# Motordriver.net
KiCad netlist of a schematic drawn in Altium Designer
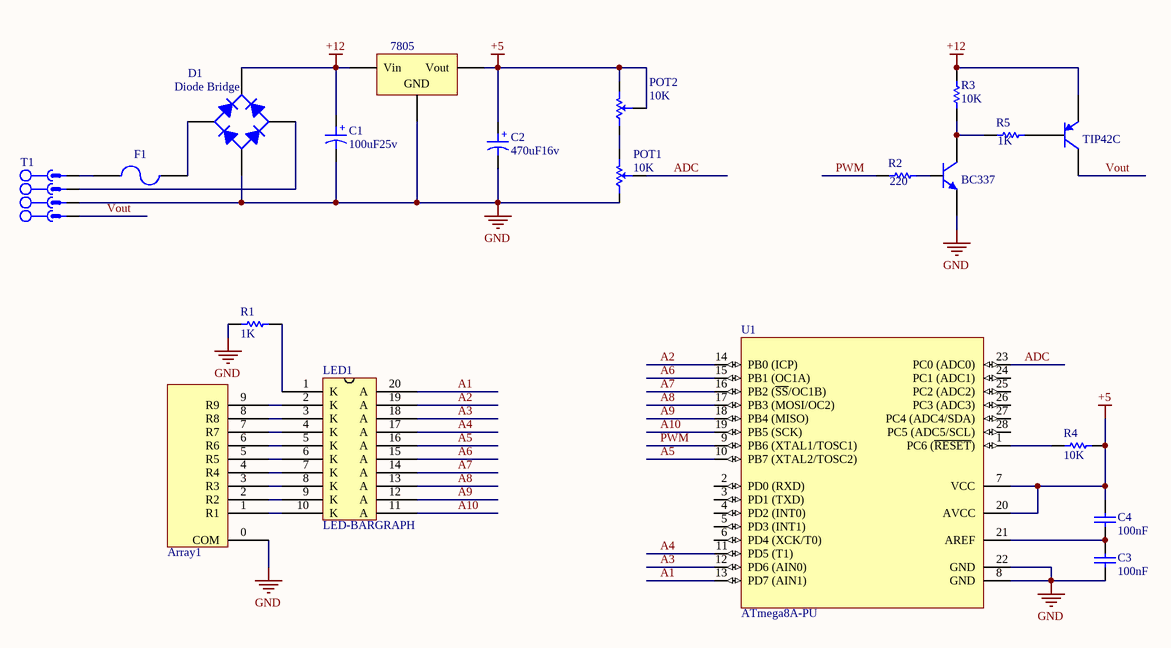
[diagram p0: Motordriver.SchDoc]

(export (version "E")
  (design (tool "Eeschema 10.0.6"))
  (components
    (comp (ref "7805")
      (value "L7805CV")
      (footprint "TO-220 AB WITH HEAT SINK")
      (description "Linear Voltage Regulator IC Positive FIXED Output 5V 1.5A TO-220AB")
      (fields (field (name "MANUFACTURER") "STMicroelectronics") (field (name "DESIGNER") "Abbas Basereh"))
      (libsource (lib "Altium") (part "L7805CV-Linear Voltage Regulator"))
    )
    (comp (ref "Array1")
      (value "Array10pin")
      (footprint "Array")
      (libsource (lib "emadars_Library") (part "Array10pin"))
    )
    (comp (ref "BC337")
      (value "TIP41C")
      (footprint "TO-220 AB WITH HEAT SINK")
      (description "NPN  power transistor")
      (fields (field (name "MANUFACTURER") "STMicroelectronics") (field (name "DESIGNER") "Abbas Basereh"))
      (libsource (lib "Altium") (part "TIP41C"))
    )
    (comp (ref "C1")
      (value "100uF25v")
      (footprint "Cap electrolitic radial 6x7-2.5")
      (description "Cap electrolitic radial")
      (fields (field (name "DESIGNER") "Abbas Basereh"))
      (libsource (lib "Altium") (part "Cap ELECTROLITIC TOTAL SIZE"))
    )
    (comp (ref "C2")
      (value "470uF16v")
      (footprint "Cap electrolitic radial 6x7-2.5")
      (description "Cap electrolitic radial")
      (fields (field (name "DESIGNER") "Abbas Basereh"))
      (libsource (lib "Altium") (part "Cap ELECTROLITIC TOTAL SIZE"))
    )
    (comp (ref "C3")
      (value "100nF")
      (footprint "CAP Ceramic 2.5MM")
      (description "CAP Ceramic Total")
      (fields (field (name "DESIGNER") "Ali Hafizi"))
      (libsource (lib "Altium") (part "CAP CERAMIC TOTAL SIZE"))
    )
    (comp (ref "C4")
      (value "100nF")
      (footprint "CAP Ceramic 2.5MM")
      (description "CAP Ceramic Total")
      (fields (field (name "DESIGNER") "Ali Hafizi"))
      (libsource (lib "Altium") (part "CAP CERAMIC TOTAL SIZE"))
    )
    (comp (ref "D1")
      (value "Diode Bridge")
      (footprint "Bridge Circle Package")
      (description "Full Wave Diode Bridge")
      (fields (field (name "DESIGNER") "Abbas Basereh"))
      (libsource (lib "Altium") (part "Diode Bridge TOTAL SIZE"))
    )
    (comp (ref "F1")
      (value "F=1.0 A")
      (footprint "Fuse 5x20 With holder pin")
      (description "Fuses 5x20")
      (fields (field (name "DESIGNER") "Abbas Basereh"))
      (libsource (lib "Altium") (part "Fuse 5x20 with holdeer pins"))
    )
    (comp (ref "LED1")
      (value "LED-BARGRAPH")
      (footprint "LED-BARGRAPH")
      (libsource (lib "emadars_Library") (part "LED-BARGRAPH"))
    )
    (comp (ref "POT1")
      (value "10K")
      (footprint "POT")
      (description "Variable Resistor")
      (libsource (lib "Altium") (part "POT"))
    )
    (comp (ref "POT2")
      (value "10K")
      (footprint "POT 4")
      (description "Variable Resistor")
      (libsource (lib "Altium") (part "POT"))
    )
    (comp (ref "R1")
      (value "1K")
      (footprint "Axial 0_5W 5_0mm")
      (description "RES Axial 0.5W")
      (fields (field (name "DESIGNER") "Abbas Basereh"))
      (libsource (lib "Altium") (part "RES Axial 0.5W"))
    )
    (comp (ref "R2")
      (value "220")
      (footprint "Axial 0_5W 5_0mm")
      (description "RES Axial 0.5W")
      (fields (field (name "DESIGNER") "Abbas Basereh"))
      (libsource (lib "Altium") (part "RES Axial 0.5W"))
    )
    (comp (ref "R3")
      (value "10K")
      (footprint "Axial 0_5W 5_0mm")
      (description "RES Axial 0.5W")
      (fields (field (name "DESIGNER") "Abbas Basereh"))
      (libsource (lib "Altium") (part "RES Axial 0.5W"))
    )
    (comp (ref "R4")
      (value "10K")
      (footprint "Axial 0_5W 5_0mm")
      (description "RES Axial 0.5W")
      (fields (field (name "DESIGNER") "Abbas Basereh"))
      (libsource (lib "Altium") (part "RES Axial 0.5W"))
    )
    (comp (ref "R5")
      (value "1K")
      (footprint "Axial 0_5W 5_0mm")
      (description "RES Axial 0.5W")
      (fields (field (name "DESIGNER") "Abbas Basereh"))
      (libsource (lib "Altium") (part "RES Axial 0.5W"))
    )
    (comp (ref "T1")
      (value "~")
      (footprint "MSTBV 2,5/4-G-5")
      (description "4 Pitch: 5 mm Color: green Contact surface: Tin Assembly")
      (fields
        (field (name "MANUFACTURER") "PHOENIX CONTACT")
        (field (name "VOLTAGE") "320 V")
        (field (name "DESIGNER") "ABBAS BASEREH")
      )
      (libsource (lib "Altium") (part "CON_Phoenix_MSTBV_04"))
    )
    (comp (ref "TIP42C")
      (value "TIP42C")
      (footprint "TO-220 AB WITH HEAT SINK")
      (description "PNP  power transistor")
      (fields (field (name "MANUFACTURER") "STMicroelectronics") (field (name "DESIGNER") "Abbas Basereh"))
      (libsource (lib "Altium") (part "TIP42C"))
    )
    (comp (ref "U1")
      (value "ATmega8A-PU")
      (footprint "28P3")
      (fields (field (name "PUBLISHER") "Abbas Basereh"))
      (libsource (lib "Altium") (part "ATmega8A-PU"))
    )
  )
  (nets
    (net (code "1") (name "+5") (class "Default")
      (node (ref "7805") (pin "3") (pinfunction "Vout_3") (pintype "passive"))
      (node (ref "C2") (pin "1") (pinfunction "1_1") (pintype "passive"))
      (node (ref "C4") (pin "2") (pinfunction "2_2") (pintype "passive"))
      (node (ref "POT2") (pin "2") (pinfunction "CW_2") (pintype "passive"))
      (node (ref "POT2") (pin "3") (pinfunction "SetPoint_3") (pintype "passive"))
      (node (ref "R4") (pin "2") (pinfunction "2_2") (pintype "passive"))
      (node (ref "U1") (pin "20") (pinfunction "AVCC_20") (pintype "power_in"))
      (node (ref "U1") (pin "7") (pinfunction "VCC_7") (pintype "power_in"))
    )
    (net (code "2") (name "+12") (class "Default")
      (node (ref "7805") (pin "1") (pinfunction "Vin_1") (pintype "passive"))
      (node (ref "C1") (pin "1") (pinfunction "1_1") (pintype "passive"))
      (node (ref "D1") (pin "1") (pinfunction "+_1") (pintype "passive"))
      (node (ref "R3") (pin "2") (pinfunction "2_2") (pintype "passive"))
      (node (ref "TIP42C") (pin "3") (pinfunction "E_3") (pintype "passive"))
    )
    (net (code "3") (name "/A1") (class "Default")
      (node (ref "LED1") (pin "20") (pinfunction "A_20") (pintype "passive"))
      (node (ref "U1") (pin "13") (pinfunction "PD7_(AIN1)_13") (pintype "bidirectional"))
    )
    (net (code "4") (name "/A2") (class "Default")
      (node (ref "LED1") (pin "19") (pinfunction "A_19") (pintype "passive"))
      (node (ref "U1") (pin "14") (pinfunction "PB0_(ICP)_14") (pintype "bidirectional"))
    )
    (net (code "5") (name "/A3") (class "Default")
      (node (ref "LED1") (pin "18") (pinfunction "A_18") (pintype "passive"))
      (node (ref "U1") (pin "12") (pinfunction "PD6_(AIN0)_12") (pintype "bidirectional"))
    )
    (net (code "6") (name "/A4") (class "Default")
      (node (ref "LED1") (pin "17") (pinfunction "A_17") (pintype "passive"))
      (node (ref "U1") (pin "11") (pinfunction "PD5_(T1)_11") (pintype "bidirectional"))
    )
    (net (code "7") (name "/A5") (class "Default")
      (node (ref "LED1") (pin "16") (pinfunction "A_16") (pintype "passive"))
      (node (ref "U1") (pin "10") (pinfunction "PB7_(XTAL2/TOSC2)_10") (pintype "bidirectional"))
    )
    (net (code "8") (name "/A6") (class "Default")
      (node (ref "LED1") (pin "15") (pinfunction "A_15") (pintype "passive"))
      (node (ref "U1") (pin "15") (pinfunction "PB1_(OC1A)_15") (pintype "bidirectional"))
    )
    (net (code "9") (name "/A7") (class "Default")
      (node (ref "LED1") (pin "14") (pinfunction "A_14") (pintype "passive"))
      (node (ref "U1") (pin "16") (pinfunction "PB2_(~{SS}/OC1B)_16") (pintype "bidirectional"))
    )
    (net (code "10") (name "/A8") (class "Default")
      (node (ref "LED1") (pin "13") (pinfunction "A_13") (pintype "passive"))
      (node (ref "U1") (pin "17") (pinfunction "PB3_(MOSI/OC2)_17") (pintype "bidirectional"))
    )
    (net (code "11") (name "/A9") (class "Default")
      (node (ref "LED1") (pin "12") (pinfunction "A_12") (pintype "passive"))
      (node (ref "U1") (pin "18") (pinfunction "PB4_(MISO)_18") (pintype "bidirectional"))
    )
    (net (code "12") (name "/A10") (class "Default")
      (node (ref "LED1") (pin "11") (pinfunction "A_11") (pintype "passive"))
      (node (ref "U1") (pin "19") (pinfunction "PB5_(SCK)_19") (pintype "bidirectional"))
    )
    (net (code "13") (name "/ADC") (class "Default")
      (node (ref "POT1") (pin "3") (pinfunction "SetPoint_3") (pintype "passive"))
      (node (ref "U1") (pin "23") (pinfunction "PC0_(ADC0)_23") (pintype "bidirectional"))
    )
    (net (code "14") (name "/PWM") (class "Default")
      (node (ref "R2") (pin "1") (pinfunction "1_1") (pintype "passive"))
      (node (ref "U1") (pin "9") (pinfunction "PB6_(XTAL1/TOSC1)_9") (pintype "bidirectional"))
    )
    (net (code "15") (name "/Vout") (class "Default")
      (node (ref "T1") (pin "4") (pinfunction "4_4") (pintype "passive"))
      (node (ref "TIP42C") (pin "2") (pinfunction "C_2") (pintype "passive"))
    )
    (net (code "16") (name "GND") (class "Default")
      (node (ref "7805") (pin "2") (pinfunction "GND_2") (pintype "passive"))
      (node (ref "Array1") (pin "0") (pinfunction "COM_0") (pintype "passive"))
      (node (ref "BC337") (pin "3") (pinfunction "E_3") (pintype "passive"))
      (node (ref "C1") (pin "2") (pinfunction "2_2") (pintype "passive"))
      (node (ref "C2") (pin "2") (pinfunction "2_2") (pintype "passive"))
      (node (ref "C3") (pin "2") (pinfunction "2_2") (pintype "passive"))
      (node (ref "D1") (pin "4") (pinfunction "-_4") (pintype "passive"))
      (node (ref "POT1") (pin "1") (pinfunction "CCW_1") (pintype "passive"))
      (node (ref "R1") (pin "1") (pinfunction "1_1") (pintype "passive"))
      (node (ref "T1") (pin "3") (pinfunction "3_3") (pintype "passive"))
      (node (ref "U1") (pin "22") (pinfunction "GND_22") (pintype "power_in"))
      (node (ref "U1") (pin "8") (pinfunction "GND_8") (pintype "power_in"))
    )
    (net (code "17") (name "Net-(Array1-R1)") (class "Default")
      (node (ref "Array1") (pin "1") (pinfunction "R1_1") (pintype "passive"))
      (node (ref "LED1") (pin "10") (pinfunction "K_10") (pintype "passive"))
    )
    (net (code "18") (name "Net-(Array1-R2)") (class "Default")
      (node (ref "Array1") (pin "2") (pinfunction "R2_2") (pintype "passive"))
      (node (ref "LED1") (pin "9") (pinfunction "K_9") (pintype "passive"))
    )
    (net (code "19") (name "Net-(Array1-R3)") (class "Default")
      (node (ref "Array1") (pin "3") (pinfunction "R3_3") (pintype "passive"))
      (node (ref "LED1") (pin "8") (pinfunction "K_8") (pintype "passive"))
    )
    (net (code "20") (name "Net-(Array1-R4)") (class "Default")
      (node (ref "Array1") (pin "4") (pinfunction "R4_4") (pintype "passive"))
      (node (ref "LED1") (pin "7") (pinfunction "K_7") (pintype "passive"))
    )
    (net (code "21") (name "Net-(Array1-R5)") (class "Default")
      (node (ref "Array1") (pin "5") (pinfunction "R5_5") (pintype "passive"))
      (node (ref "LED1") (pin "6") (pinfunction "K_6") (pintype "passive"))
    )
    (net (code "22") (name "Net-(Array1-R6)") (class "Default")
      (node (ref "Array1") (pin "6") (pinfunction "R6_6") (pintype "passive"))
      (node (ref "LED1") (pin "5") (pinfunction "K_5") (pintype "passive"))
    )
    (net (code "23") (name "Net-(Array1-R7)") (class "Default")
      (node (ref "Array1") (pin "7") (pinfunction "R7_7") (pintype "passive"))
      (node (ref "LED1") (pin "4") (pinfunction "K_4") (pintype "passive"))
    )
    (net (code "24") (name "Net-(Array1-R8)") (class "Default")
      (node (ref "Array1") (pin "8") (pinfunction "R8_8") (pintype "passive"))
      (node (ref "LED1") (pin "3") (pinfunction "K_3") (pintype "passive"))
    )
    (net (code "25") (name "Net-(Array1-R9)") (class "Default")
      (node (ref "Array1") (pin "9") (pinfunction "R9_9") (pintype "passive"))
      (node (ref "LED1") (pin "2") (pinfunction "K_2") (pintype "passive"))
    )
    (net (code "26") (name "Net-(BC337-B)") (class "Default")
      (node (ref "BC337") (pin "1") (pinfunction "B_1") (pintype "passive"))
      (node (ref "R2") (pin "2") (pinfunction "2_2") (pintype "passive"))
    )
    (net (code "27") (name "Net-(BC337-C)") (class "Default")
      (node (ref "BC337") (pin "2") (pinfunction "C_2") (pintype "passive"))
      (node (ref "R3") (pin "1") (pinfunction "1_1") (pintype "passive"))
      (node (ref "R5") (pin "1") (pinfunction "1_1") (pintype "passive"))
    )
    (net (code "28") (name "Net-(D1-AC-Pad2)") (class "Default")
      (node (ref "D1") (pin "2") (pinfunction "AC_2") (pintype "passive"))
      (node (ref "F1") (pin "2") (pinfunction "2_2") (pintype "passive"))
    )
    (net (code "29") (name "Net-(D1-AC-Pad3)") (class "Default")
      (node (ref "D1") (pin "3") (pinfunction "AC_3") (pintype "passive"))
      (node (ref "T1") (pin "2") (pinfunction "2_2") (pintype "passive"))
    )
    (net (code "30") (name "Net-(F1-Pad1)") (class "Default")
      (node (ref "F1") (pin "1") (pinfunction "1_1") (pintype "passive"))
      (node (ref "T1") (pin "1") (pinfunction "1_1") (pintype "passive"))
    )
    (net (code "31") (name "Net-(LED1-K-Pad1)") (class "Default")
      (node (ref "LED1") (pin "1") (pinfunction "K_1") (pintype "passive"))
      (node (ref "R1") (pin "2") (pinfunction "2_2") (pintype "passive"))
    )
    (net (code "32") (name "Net-(POT1-CW)") (class "Default")
      (node (ref "POT1") (pin "2") (pinfunction "CW_2") (pintype "passive"))
      (node (ref "POT2") (pin "1") (pinfunction "CCW_1") (pintype "passive"))
    )
    (net (code "33") (name "Net-(TIP42C-B)") (class "Default")
      (node (ref "R5") (pin "2") (pinfunction "2_2") (pintype "passive"))
      (node (ref "TIP42C") (pin "1") (pinfunction "B_1") (pintype "passive"))
    )
    (net (code "34") (name "Net-(U1-AREF)") (class "Default")
      (node (ref "C3") (pin "1") (pinfunction "1_1") (pintype "passive"))
      (node (ref "C4") (pin "1") (pinfunction "1_1") (pintype "passive"))
      (node (ref "U1") (pin "21") (pinfunction "AREF_21") (pintype "passive"))
    )
    (net (code "35") (name "Net-(U1-PC6_(~{RESET}))") (class "Default")
      (node (ref "R4") (pin "1") (pinfunction "1_1") (pintype "passive"))
      (node (ref "U1") (pin "1") (pinfunction "PC6_(~{RESET})_1") (pintype "bidirectional"))
    )
    (net (code "36") (name "unconnected-(U1-PC1_(ADC1)-Pad24)") (class "Default")
      (node (ref "U1") (pin "24") (pinfunction "PC1_(ADC1)_24") (pintype "bidirectional"))
    )
    (net (code "37") (name "unconnected-(U1-PC2_(ADC2)-Pad25)") (class "Default")
      (node (ref "U1") (pin "25") (pinfunction "PC2_(ADC2)_25") (pintype "bidirectional"))
    )
    (net (code "38") (name "unconnected-(U1-PC3_(ADC3)-Pad26)") (class "Default")
      (node (ref "U1") (pin "26") (pinfunction "PC3_(ADC3)_26") (pintype "bidirectional"))
    )
    (net (code "39") (name "unconnected-(U1-PC4_(ADC4{slash}SDA)-Pad27)") (class "Default")
      (node (ref "U1") (pin "27") (pinfunction "PC4_(ADC4/SDA)_27") (pintype "bidirectional"))
    )
    (net (code "40") (name "unconnected-(U1-PC5_(ADC5{slash}SCL)-Pad28)") (class "Default")
      (node (ref "U1") (pin "28") (pinfunction "PC5_(ADC5/SCL)_28") (pintype "bidirectional"))
    )
    (net (code "41") (name "unconnected-(U1-PD0_(RXD)-Pad2)") (class "Default")
      (node (ref "U1") (pin "2") (pinfunction "PD0_(RXD)_2") (pintype "bidirectional"))
    )
    (net (code "42") (name "unconnected-(U1-PD1_(TXD)-Pad3)") (class "Default")
      (node (ref "U1") (pin "3") (pinfunction "PD1_(TXD)_3") (pintype "bidirectional"))
    )
    (net (code "43") (name "unconnected-(U1-PD2_(INT0)-Pad4)") (class "Default")
      (node (ref "U1") (pin "4") (pinfunction "PD2_(INT0)_4") (pintype "bidirectional"))
    )
    (net (code "44") (name "unconnected-(U1-PD3_(INT1)-Pad5)") (class "Default")
      (node (ref "U1") (pin "5") (pinfunction "PD3_(INT1)_5") (pintype "bidirectional"))
    )
    (net (code "45") (name "unconnected-(U1-PD4_(XCK{slash}T0)-Pad6)") (class "Default")
      (node (ref "U1") (pin "6") (pinfunction "PD4_(XCK/T0)_6") (pintype "bidirectional"))
    )
  )
)
